# Connectors.net
KiCad netlist of a schematic drawn in Altium Designer
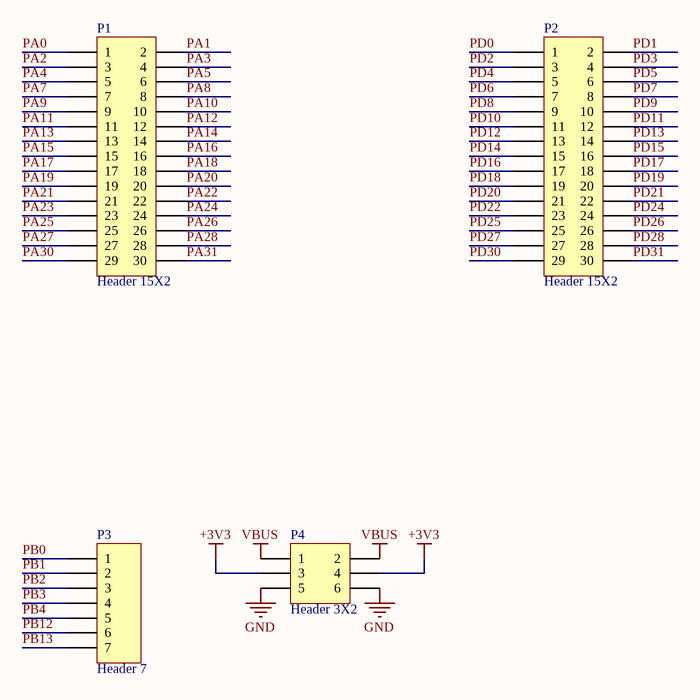
[diagram p0: Connectors.SchDoc]

(export (version "E")
  (design (tool "Eeschema 10.0.6"))
  (components
    (comp (ref "P1")
      (value "Header 15X2")
      (footprint "HDR2X15")
      (description "Header, 15-Pin, Dual row")
      (fields (field (name "PUBLISHER") "Altium Limited"))
      (libsource (lib "Miscellaneous Connectors") (part "Header 15X2"))
    )
    (comp (ref "P2")
      (value "Header 15X2")
      (footprint "HDR2X15")
      (description "Header, 15-Pin, Dual row")
      (fields (field (name "PUBLISHER") "Altium Limited"))
      (libsource (lib "Miscellaneous Connectors") (part "Header 15X2"))
    )
    (comp (ref "P3")
      (value "Header 7")
      (footprint "HDR1X7")
      (description "Header, 7-Pin")
      (fields (field (name "PUBLISHER") "Altium Limited"))
      (libsource (lib "Miscellaneous Connectors") (part "Header 7"))
    )
    (comp (ref "P4")
      (value "Header 3X2")
      (footprint "HDR2X3")
      (description "Header, 3-Pin, Dual row")
      (fields (field (name "PUBLISHER") "Altium Limited"))
      (libsource (lib "Miscellaneous Connectors") (part "Header 3X2"))
    )
  )
  (nets
    (net (code "1") (name "+3V3") (class "Default")
      (node (ref "P4") (pin "3") (pinfunction "3_3") (pintype "passive"))
      (node (ref "P4") (pin "4") (pinfunction "4_4") (pintype "passive"))
    )
    (net (code "2") (name "/PA0") (class "Default")
      (node (ref "P1") (pin "1") (pinfunction "1_1") (pintype "passive"))
    )
    (net (code "3") (name "/PA1") (class "Default")
      (node (ref "P1") (pin "2") (pinfunction "2_2") (pintype "passive"))
    )
    (net (code "4") (name "/PA2") (class "Default")
      (node (ref "P1") (pin "3") (pinfunction "3_3") (pintype "passive"))
    )
    (net (code "5") (name "/PA3") (class "Default")
      (node (ref "P1") (pin "4") (pinfunction "4_4") (pintype "passive"))
    )
    (net (code "6") (name "/PA4") (class "Default")
      (node (ref "P1") (pin "5") (pinfunction "5_5") (pintype "passive"))
    )
    (net (code "7") (name "/PA5") (class "Default")
      (node (ref "P1") (pin "6") (pinfunction "6_6") (pintype "passive"))
    )
    (net (code "8") (name "/PA7") (class "Default")
      (node (ref "P1") (pin "7") (pinfunction "7_7") (pintype "passive"))
    )
    (net (code "9") (name "/PA8") (class "Default")
      (node (ref "P1") (pin "8") (pinfunction "8_8") (pintype "passive"))
    )
    (net (code "10") (name "/PA9") (class "Default")
      (node (ref "P1") (pin "9") (pinfunction "9_9") (pintype "passive"))
    )
    (net (code "11") (name "/PA10") (class "Default")
      (node (ref "P1") (pin "10") (pinfunction "10_10") (pintype "passive"))
    )
    (net (code "12") (name "/PA11") (class "Default")
      (node (ref "P1") (pin "11") (pinfunction "11_11") (pintype "passive"))
    )
    (net (code "13") (name "/PA12") (class "Default")
      (node (ref "P1") (pin "12") (pinfunction "12_12") (pintype "passive"))
    )
    (net (code "14") (name "/PA13") (class "Default")
      (node (ref "P1") (pin "13") (pinfunction "13_13") (pintype "passive"))
    )
    (net (code "15") (name "/PA14") (class "Default")
      (node (ref "P1") (pin "14") (pinfunction "14_14") (pintype "passive"))
    )
    (net (code "16") (name "/PA15") (class "Default")
      (node (ref "P1") (pin "15") (pinfunction "15_15") (pintype "passive"))
    )
    (net (code "17") (name "/PA16") (class "Default")
      (node (ref "P1") (pin "16") (pinfunction "16_16") (pintype "passive"))
    )
    (net (code "18") (name "/PA17") (class "Default")
      (node (ref "P1") (pin "17") (pinfunction "17_17") (pintype "passive"))
    )
    (net (code "19") (name "/PA18") (class "Default")
      (node (ref "P1") (pin "18") (pinfunction "18_18") (pintype "passive"))
    )
    (net (code "20") (name "/PA19") (class "Default")
      (node (ref "P1") (pin "19") (pinfunction "19_19") (pintype "passive"))
    )
    (net (code "21") (name "/PA20") (class "Default")
      (node (ref "P1") (pin "20") (pinfunction "20_20") (pintype "passive"))
    )
    (net (code "22") (name "/PA21") (class "Default")
      (node (ref "P1") (pin "21") (pinfunction "21_21") (pintype "passive"))
    )
    (net (code "23") (name "/PA22") (class "Default")
      (node (ref "P1") (pin "22") (pinfunction "22_22") (pintype "passive"))
    )
    (net (code "24") (name "/PA23") (class "Default")
      (node (ref "P1") (pin "23") (pinfunction "23_23") (pintype "passive"))
    )
    (net (code "25") (name "/PA24") (class "Default")
      (node (ref "P1") (pin "24") (pinfunction "24_24") (pintype "passive"))
    )
    (net (code "26") (name "/PA25") (class "Default")
      (node (ref "P1") (pin "25") (pinfunction "25_25") (pintype "passive"))
    )
    (net (code "27") (name "/PA26") (class "Default")
      (node (ref "P1") (pin "26") (pinfunction "26_26") (pintype "passive"))
    )
    (net (code "28") (name "/PA27") (class "Default")
      (node (ref "P1") (pin "27") (pinfunction "27_27") (pintype "passive"))
    )
    (net (code "29") (name "/PA28") (class "Default")
      (node (ref "P1") (pin "28") (pinfunction "28_28") (pintype "passive"))
    )
    (net (code "30") (name "/PA30") (class "Default")
      (node (ref "P1") (pin "29") (pinfunction "29_29") (pintype "passive"))
    )
    (net (code "31") (name "/PA31") (class "Default")
      (node (ref "P1") (pin "30") (pinfunction "30_30") (pintype "passive"))
    )
    (net (code "32") (name "/PB0") (class "Default")
      (node (ref "P3") (pin "1") (pinfunction "1_1") (pintype "passive"))
    )
    (net (code "33") (name "/PB1") (class "Default")
      (node (ref "P3") (pin "2") (pinfunction "2_2") (pintype "passive"))
    )
    (net (code "34") (name "/PB2") (class "Default")
      (node (ref "P3") (pin "3") (pinfunction "3_3") (pintype "passive"))
    )
    (net (code "35") (name "/PB3") (class "Default")
      (node (ref "P3") (pin "4") (pinfunction "4_4") (pintype "passive"))
    )
    (net (code "36") (name "/PB4") (class "Default")
      (node (ref "P3") (pin "5") (pinfunction "5_5") (pintype "passive"))
    )
    (net (code "37") (name "/PB12") (class "Default")
      (node (ref "P3") (pin "6") (pinfunction "6_6") (pintype "passive"))
    )
    (net (code "38") (name "/PB13") (class "Default")
      (node (ref "P3") (pin "7") (pinfunction "7_7") (pintype "passive"))
    )
    (net (code "39") (name "/PD0") (class "Default")
      (node (ref "P2") (pin "1") (pinfunction "1_1") (pintype "passive"))
    )
    (net (code "40") (name "/PD1") (class "Default")
      (node (ref "P2") (pin "2") (pinfunction "2_2") (pintype "passive"))
    )
    (net (code "41") (name "/PD2") (class "Default")
      (node (ref "P2") (pin "3") (pinfunction "3_3") (pintype "passive"))
    )
    (net (code "42") (name "/PD3") (class "Default")
      (node (ref "P2") (pin "4") (pinfunction "4_4") (pintype "passive"))
    )
    (net (code "43") (name "/PD4") (class "Default")
      (node (ref "P2") (pin "5") (pinfunction "5_5") (pintype "passive"))
    )
    (net (code "44") (name "/PD5") (class "Default")
      (node (ref "P2") (pin "6") (pinfunction "6_6") (pintype "passive"))
    )
    (net (code "45") (name "/PD6") (class "Default")
      (node (ref "P2") (pin "7") (pinfunction "7_7") (pintype "passive"))
    )
    (net (code "46") (name "/PD7") (class "Default")
      (node (ref "P2") (pin "8") (pinfunction "8_8") (pintype "passive"))
    )
    (net (code "47") (name "/PD8") (class "Default")
      (node (ref "P2") (pin "9") (pinfunction "9_9") (pintype "passive"))
    )
    (net (code "48") (name "/PD9") (class "Default")
      (node (ref "P2") (pin "10") (pinfunction "10_10") (pintype "passive"))
    )
    (net (code "49") (name "/PD10") (class "Default")
      (node (ref "P2") (pin "11") (pinfunction "11_11") (pintype "passive"))
    )
    (net (code "50") (name "/PD11") (class "Default")
      (node (ref "P2") (pin "12") (pinfunction "12_12") (pintype "passive"))
    )
    (net (code "51") (name "/PD12") (class "Default")
      (node (ref "P2") (pin "13") (pinfunction "13_13") (pintype "passive"))
    )
    (net (code "52") (name "/PD13") (class "Default")
      (node (ref "P2") (pin "14") (pinfunction "14_14") (pintype "passive"))
    )
    (net (code "53") (name "/PD14") (class "Default")
      (node (ref "P2") (pin "15") (pinfunction "15_15") (pintype "passive"))
    )
    (net (code "54") (name "/PD15") (class "Default")
      (node (ref "P2") (pin "16") (pinfunction "16_16") (pintype "passive"))
    )
    (net (code "55") (name "/PD16") (class "Default")
      (node (ref "P2") (pin "17") (pinfunction "17_17") (pintype "passive"))
    )
    (net (code "56") (name "/PD17") (class "Default")
      (node (ref "P2") (pin "18") (pinfunction "18_18") (pintype "passive"))
    )
    (net (code "57") (name "/PD18") (class "Default")
      (node (ref "P2") (pin "19") (pinfunction "19_19") (pintype "passive"))
    )
    (net (code "58") (name "/PD19") (class "Default")
      (node (ref "P2") (pin "20") (pinfunction "20_20") (pintype "passive"))
    )
    (net (code "59") (name "/PD20") (class "Default")
      (node (ref "P2") (pin "21") (pinfunction "21_21") (pintype "passive"))
    )
    (net (code "60") (name "/PD21") (class "Default")
      (node (ref "P2") (pin "22") (pinfunction "22_22") (pintype "passive"))
    )
    (net (code "61") (name "/PD22") (class "Default")
      (node (ref "P2") (pin "23") (pinfunction "23_23") (pintype "passive"))
    )
    (net (code "62") (name "/PD24") (class "Default")
      (node (ref "P2") (pin "24") (pinfunction "24_24") (pintype "passive"))
    )
    (net (code "63") (name "/PD25") (class "Default")
      (node (ref "P2") (pin "25") (pinfunction "25_25") (pintype "passive"))
    )
    (net (code "64") (name "/PD26") (class "Default")
      (node (ref "P2") (pin "26") (pinfunction "26_26") (pintype "passive"))
    )
    (net (code "65") (name "/PD27") (class "Default")
      (node (ref "P2") (pin "27") (pinfunction "27_27") (pintype "passive"))
    )
    (net (code "66") (name "/PD28") (class "Default")
      (node (ref "P2") (pin "28") (pinfunction "28_28") (pintype "passive"))
    )
    (net (code "67") (name "/PD30") (class "Default")
      (node (ref "P2") (pin "29") (pinfunction "29_29") (pintype "passive"))
    )
    (net (code "68") (name "/PD31") (class "Default")
      (node (ref "P2") (pin "30") (pinfunction "30_30") (pintype "passive"))
    )
    (net (code "69") (name "GND") (class "Default")
      (node (ref "P4") (pin "5") (pinfunction "5_5") (pintype "passive"))
      (node (ref "P4") (pin "6") (pinfunction "6_6") (pintype "passive"))
    )
    (net (code "70") (name "VBUS") (class "Default")
      (node (ref "P4") (pin "1") (pinfunction "1_1") (pintype "passive"))
      (node (ref "P4") (pin "2") (pinfunction "2_2") (pintype "passive"))
    )
  )
)
